# RS232_Comms.net
KiCad netlist of a schematic drawn in Altium Designer
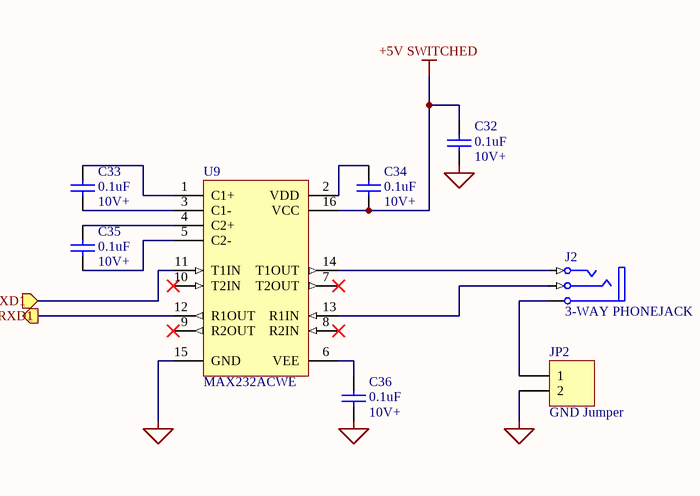
[diagram p0: RS232 Comms.SchDoc]

(export (version "E")
  (design (tool "Eeschema 10.0.6"))
  (components
    (comp (ref "C32")
      (value "0.1uF")
      (footprint "RAD-0.3")
      (description "Capacitor")
      (fields (field (name "PUBLISHER") "Altium Limited"))
      (libsource (lib "Miscellaneous Devices") (part "Cap"))
    )
    (comp (ref "C33")
      (value "0.1uF")
      (footprint "RAD-0.3")
      (description "Capacitor")
      (fields (field (name "PUBLISHER") "Altium Limited"))
      (libsource (lib "Miscellaneous Devices") (part "Cap"))
    )
    (comp (ref "C34")
      (value "0.1uF")
      (footprint "RAD-0.3")
      (description "Capacitor")
      (fields (field (name "PUBLISHER") "Altium Limited"))
      (libsource (lib "Miscellaneous Devices") (part "Cap"))
    )
    (comp (ref "C35")
      (value "0.1uF")
      (footprint "RAD-0.3")
      (description "Capacitor")
      (fields (field (name "PUBLISHER") "Altium Limited"))
      (libsource (lib "Miscellaneous Devices") (part "Cap"))
    )
    (comp (ref "C36")
      (value "0.1uF")
      (footprint "RAD-0.3")
      (description "Capacitor")
      (fields (field (name "PUBLISHER") "Altium Limited"))
      (libsource (lib "Miscellaneous Devices") (part "Cap"))
    )
    (comp (ref "J2")
      (value "3-WAY PHONEJACK")
      (footprint "JACK/6-V3")
      (description "Jack Socket, 1/4\" [6.5mm], Thru-Hole, Vertical, 3-Conductor Open Circuit (Non-Normalling)")
      (fields (field (name "PUBLISHER") "Altium Limited"))
      (libsource (lib "Miscellaneous Connectors") (part "Phonejack3"))
    )
    (comp (ref "JP2")
      (value "GND Jumper")
      (footprint "HDR1X2")
      (description "Header, 2-Pin")
      (fields (field (name "PUBLISHER") "Altium Limited"))
      (libsource (lib "Miscellaneous Connectors") (part "Header 2"))
    )
    (comp (ref "U9")
      (value "MAX232ACWE")
      (footprint "WSO16_N")
      (description "+5V Powered, Multi-Channel RS-232 Driver/Receiver")
      (fields (field (name "PUBLISHER") "Altium Limited"))
      (libsource (lib "Maxim Communication Transceiver") (part "MAX232ACWE"))
    )
  )
  (nets
    (net (code "1") (name "+5V SWITCHED") (class "Default")
      (node (ref "C32") (pin "2") (pinfunction "2_2") (pintype "passive"))
      (node (ref "C34") (pin "1") (pinfunction "1_1") (pintype "passive"))
      (node (ref "U9") (pin "16") (pinfunction "VCC_16") (pintype "power_in"))
    )
    (net (code "2") (name "/CPU RXD1") (class "Default")
      (node (ref "U9") (pin "12") (pinfunction "R1OUT_12") (pintype "output"))
    )
    (net (code "3") (name "/CPU TXD1") (class "Default")
      (node (ref "U9") (pin "11") (pinfunction "T1IN_11") (pintype "input"))
    )
    (net (code "4") (name "<NO NET>") (class "Default")
      (node (ref "C32") (pin "1") (pinfunction "1_1") (pintype "passive"))
      (node (ref "C36") (pin "1") (pinfunction "1_1") (pintype "passive"))
      (node (ref "JP2") (pin "2") (pinfunction "2_2") (pintype "passive"))
      (node (ref "U9") (pin "15") (pinfunction "GND_15") (pintype "power_in"))
    )
    (net (code "5") (name "Net-(J2-R)") (class "Default")
      (node (ref "J2") (pin "3") (pinfunction "R_3") (pintype "input"))
      (node (ref "U9") (pin "13") (pinfunction "R1IN_13") (pintype "input"))
    )
    (net (code "6") (name "Net-(J2-S)") (class "Default")
      (node (ref "J2") (pin "5") (pinfunction "S_5") (pintype "power_in"))
      (node (ref "JP2") (pin "1") (pinfunction "1_1") (pintype "passive"))
    )
    (net (code "7") (name "Net-(J2-T)") (class "Default")
      (node (ref "J2") (pin "1") (pinfunction "T_1") (pintype "input"))
      (node (ref "U9") (pin "14") (pinfunction "T1OUT_14") (pintype "output"))
    )
    (net (code "8") (name "Net-(U9-C1+)") (class "Default")
      (node (ref "C33") (pin "2") (pinfunction "2_2") (pintype "passive"))
      (node (ref "U9") (pin "1") (pinfunction "C1+_1") (pintype "passive"))
    )
    (net (code "9") (name "Net-(U9-C1-)") (class "Default")
      (node (ref "C33") (pin "1") (pinfunction "1_1") (pintype "passive"))
      (node (ref "U9") (pin "3") (pinfunction "C1-_3") (pintype "passive"))
    )
    (net (code "10") (name "Net-(U9-C2+)") (class "Default")
      (node (ref "C35") (pin "2") (pinfunction "2_2") (pintype "passive"))
      (node (ref "U9") (pin "4") (pinfunction "C2+_4") (pintype "passive"))
    )
    (net (code "11") (name "Net-(U9-C2-)") (class "Default")
      (node (ref "C35") (pin "1") (pinfunction "1_1") (pintype "passive"))
      (node (ref "U9") (pin "5") (pinfunction "C2-_5") (pintype "passive"))
    )
    (net (code "12") (name "Net-(U9-VDD)") (class "Default")
      (node (ref "C34") (pin "2") (pinfunction "2_2") (pintype "passive"))
      (node (ref "U9") (pin "2") (pinfunction "VDD_2") (pintype "power_in"))
    )
    (net (code "13") (name "Net-(U9-VEE)") (class "Default")
      (node (ref "C36") (pin "2") (pinfunction "2_2") (pintype "passive"))
      (node (ref "U9") (pin "6") (pinfunction "VEE_6") (pintype "power_in"))
    )
    (net (code "14") (name "unconnected-(U9-R2IN-Pad8)") (class "Default")
      (node (ref "U9") (pin "8") (pinfunction "R2IN_8") (pintype "input+no_connect"))
    )
    (net (code "15") (name "unconnected-(U9-R2OUT-Pad9)") (class "Default")
      (node (ref "U9") (pin "9") (pinfunction "R2OUT_9") (pintype "output+no_connect"))
    )
    (net (code "16") (name "unconnected-(U9-T2IN-Pad10)") (class "Default")
      (node (ref "U9") (pin "10") (pinfunction "T2IN_10") (pintype "input+no_connect"))
    )
    (net (code "17") (name "unconnected-(U9-T2OUT-Pad7)") (class "Default")
      (node (ref "U9") (pin "7") (pinfunction "T2OUT_7") (pintype "output+no_connect"))
    )
  )
)
